# kilo.net
KiCad netlist of a schematic drawn in EAGLE
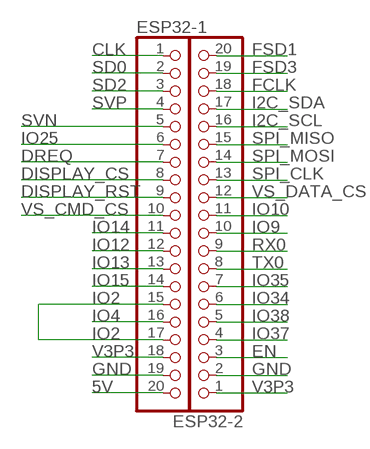
[diagram p0: schematic, sheet 1]
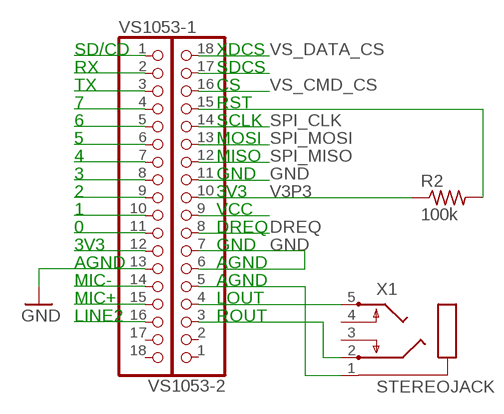
[diagram p1: schematic, sheet 2]
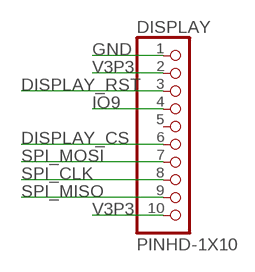
[diagram p2: schematic, sheet 3]
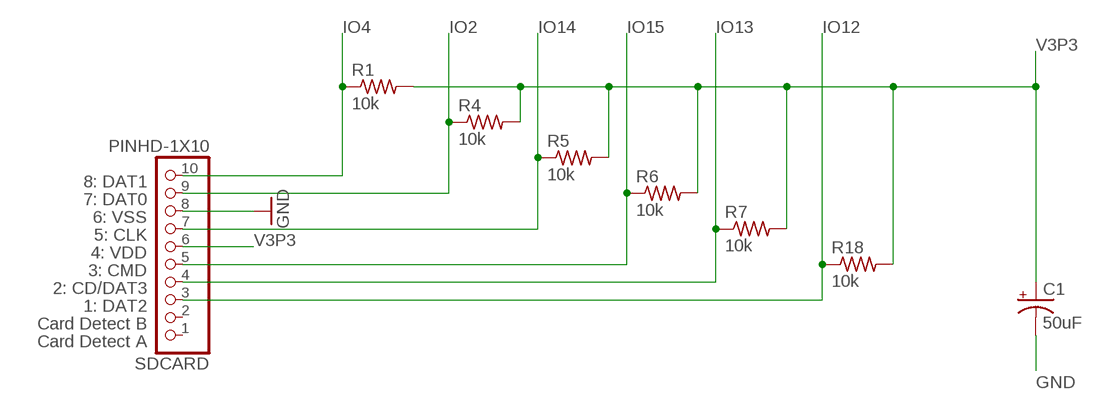
[diagram p3: schematic, sheet 4]
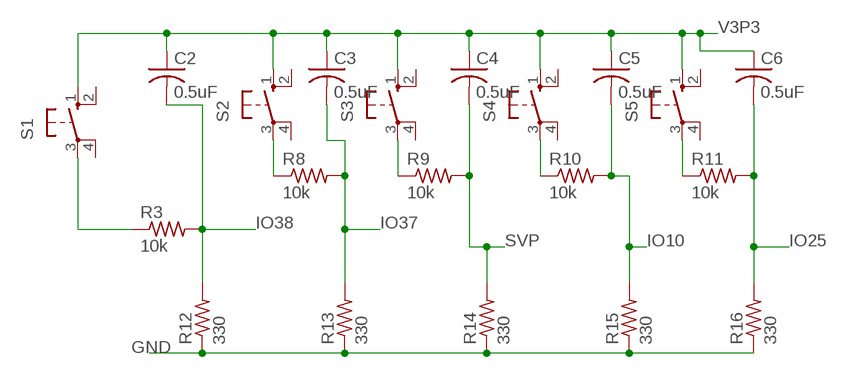
[diagram p4: schematic, sheet 5]

(export (version "E")
  (design (tool "Eeschema 10.0.6"))
  (components
    (comp (ref "C1")
      (value "50uF")
      (footprint "eagle-import:E2,5-7")
      (libsource (lib "eagle-import") (part "CPOL-USE2.5-7"))
    )
    (comp (ref "R1")
      (value "10k")
      (footprint "eagle-import:0207_10")
      (libsource (lib "eagle-import") (part "R-US_0207/10"))
    )
    (comp (ref "R4")
      (value "10k")
      (footprint "eagle-import:0207_10")
      (libsource (lib "eagle-import") (part "R-US_0207/10"))
    )
    (comp (ref "R5")
      (value "10k")
      (footprint "eagle-import:0207_10")
      (libsource (lib "eagle-import") (part "R-US_0207/10"))
    )
    (comp (ref "R6")
      (value "10k")
      (footprint "eagle-import:0207_10")
      (libsource (lib "eagle-import") (part "R-US_0207/10"))
    )
    (comp (ref "R7")
      (value "10k")
      (footprint "eagle-import:0207_10")
      (libsource (lib "eagle-import") (part "R-US_0207/10"))
    )
    (comp (ref "R18")
      (value "10k")
      (footprint "eagle-import:0207_10")
      (libsource (lib "eagle-import") (part "R-US_0207/10"))
    )
    (comp (ref "SDCARD")
      (value "PINHD-1X10")
      (footprint "eagle-import:1X10-BIG")
      (libsource (lib "eagle-import") (part "PINHD-1X10"))
    )
    (comp (ref "R2")
      (value "100k")
      (footprint "eagle-import:0207_10")
      (libsource (lib "eagle-import") (part "R-US_0207/10"))
    )
    (comp (ref "VS1053-1")
      (value "PINHD-1X18")
      (footprint "eagle-import:1X18")
      (libsource (lib "eagle-import") (part "PINHD-1X18"))
    )
    (comp (ref "VS1053-2")
      (value "PINHD-1X18")
      (footprint "eagle-import:1X18")
      (libsource (lib "eagle-import") (part "PINHD-1X18"))
    )
    (comp (ref "X1")
      (value "STEREOJACK")
      (footprint "eagle-import:STX3100")
      (libsource (lib "eagle-import") (part "STEREOJACK"))
    )
    (comp (ref "DISPLAY")
      (value "PINHD-1X10")
      (footprint "eagle-import:1X10-BIG")
      (libsource (lib "eagle-import") (part "PINHD-1X10"))
    )
    (comp (ref "C2")
      (value "0.5uF")
      (footprint "eagle-import:C025-024X044")
      (libsource (lib "eagle-import") (part "C-US025-024X044"))
    )
    (comp (ref "C3")
      (value "0.5uF")
      (footprint "eagle-import:C025-024X044")
      (libsource (lib "eagle-import") (part "C-US025-024X044"))
    )
    (comp (ref "C4")
      (value "0.5uF")
      (footprint "eagle-import:C025-024X044")
      (libsource (lib "eagle-import") (part "C-US025-024X044"))
    )
    (comp (ref "C5")
      (value "0.5uF")
      (footprint "eagle-import:C025-024X044")
      (libsource (lib "eagle-import") (part "C-US025-024X044"))
    )
    (comp (ref "C6")
      (value "0.5uF")
      (footprint "eagle-import:C025-024X044")
      (libsource (lib "eagle-import") (part "C-US025-024X044"))
    )
    (comp (ref "R3")
      (value "10k")
      (footprint "eagle-import:0207_10")
      (libsource (lib "eagle-import") (part "R-US_0207/10"))
    )
    (comp (ref "R8")
      (value "10k")
      (footprint "eagle-import:0207_10")
      (libsource (lib "eagle-import") (part "R-US_0207/10"))
    )
    (comp (ref "R9")
      (value "10k")
      (footprint "eagle-import:0207_10")
      (libsource (lib "eagle-import") (part "R-US_0207/10"))
    )
    (comp (ref "R10")
      (value "10k")
      (footprint "eagle-import:0207_10")
      (libsource (lib "eagle-import") (part "R-US_0207/10"))
    )
    (comp (ref "R11")
      (value "10k")
      (footprint "eagle-import:0207_10")
      (libsource (lib "eagle-import") (part "R-US_0207/10"))
    )
    (comp (ref "R12")
      (value "330")
      (footprint "eagle-import:0207_10")
      (libsource (lib "eagle-import") (part "R-US_0207/10"))
    )
    (comp (ref "R13")
      (value "330")
      (footprint "eagle-import:0207_10")
      (libsource (lib "eagle-import") (part "R-US_0207/10"))
    )
    (comp (ref "R14")
      (value "330")
      (footprint "eagle-import:0207_10")
      (libsource (lib "eagle-import") (part "R-US_0207/10"))
    )
    (comp (ref "R15")
      (value "330")
      (footprint "eagle-import:0207_10")
      (libsource (lib "eagle-import") (part "R-US_0207/10"))
    )
    (comp (ref "R16")
      (value "330")
      (footprint "eagle-import:0207_10")
      (libsource (lib "eagle-import") (part "R-US_0207/10"))
    )
    (comp (ref "S1")
      (value "10-XX")
      (footprint "eagle-import:B3F-10XX")
      (fields (field (name "MPN") "B3F-1000"))
      (libsource (lib "eagle-import") (part "10-XX"))
    )
    (comp (ref "S2")
      (value "10-XX")
      (footprint "eagle-import:B3F-10XX")
      (fields (field (name "MPN") "B3F-1000"))
      (libsource (lib "eagle-import") (part "10-XX"))
    )
    (comp (ref "S3")
      (value "10-XX")
      (footprint "eagle-import:B3F-10XX")
      (fields (field (name "MPN") "B3F-1000"))
      (libsource (lib "eagle-import") (part "10-XX"))
    )
    (comp (ref "S4")
      (value "10-XX")
      (footprint "eagle-import:B3F-10XX")
      (fields (field (name "MPN") "B3F-1000"))
      (libsource (lib "eagle-import") (part "10-XX"))
    )
    (comp (ref "S5")
      (value "10-XX")
      (footprint "eagle-import:B3F-10XX")
      (fields (field (name "MPN") "B3F-1000"))
      (libsource (lib "eagle-import") (part "10-XX"))
    )
    (comp (ref "ESP32-1")
      (value "PINHD-1X20")
      (footprint "eagle-import:1X20")
      (libsource (lib "eagle-import") (part "PINHD-1X20"))
    )
    (comp (ref "ESP32-2")
      (value "PINHD-1X20")
      (footprint "eagle-import:1X20")
      (libsource (lib "eagle-import") (part "PINHD-1X20"))
    )
  )
  (nets
    (net (code "1") (name "5V") (class "Default")
      (node (ref "ESP32-1") (pin "20") (pinfunction "20_20") (pintype "passive"))
    )
    (net (code "2") (name "CLK") (class "Default")
      (node (ref "ESP32-1") (pin "1") (pinfunction "1_1") (pintype "passive"))
    )
    (net (code "3") (name "DISPLAY_CS") (class "Default")
      (node (ref "DISPLAY") (pin "6") (pinfunction "6_6") (pintype "passive"))
      (node (ref "ESP32-1") (pin "8") (pinfunction "8_8") (pintype "passive"))
    )
    (net (code "4") (name "DISPLAY_RST") (class "Default")
      (node (ref "DISPLAY") (pin "3") (pinfunction "3_3") (pintype "passive"))
      (node (ref "ESP32-1") (pin "9") (pinfunction "9_9") (pintype "passive"))
    )
    (net (code "5") (name "DREQ") (class "Default")
      (node (ref "ESP32-1") (pin "7") (pinfunction "7_7") (pintype "passive"))
      (node (ref "VS1053-2") (pin "8") (pinfunction "8_8") (pintype "passive"))
    )
    (net (code "6") (name "EN") (class "Default")
      (node (ref "ESP32-2") (pin "3") (pinfunction "3_3") (pintype "passive"))
    )
    (net (code "7") (name "FCLK") (class "Default")
      (node (ref "ESP32-2") (pin "18") (pinfunction "18_18") (pintype "passive"))
    )
    (net (code "8") (name "FSD1") (class "Default")
      (node (ref "ESP32-2") (pin "20") (pinfunction "20_20") (pintype "passive"))
    )
    (net (code "9") (name "FSD3") (class "Default")
      (node (ref "ESP32-2") (pin "19") (pinfunction "19_19") (pintype "passive"))
    )
    (net (code "10") (name "GND") (class "Default")
      (node (ref "C1") (pin "-") (pinfunction "-_-") (pintype "passive"))
      (node (ref "DISPLAY") (pin "1") (pinfunction "1_1") (pintype "passive"))
      (node (ref "ESP32-1") (pin "19") (pinfunction "19_19") (pintype "passive"))
      (node (ref "ESP32-2") (pin "2") (pinfunction "2_2") (pintype "passive"))
      (node (ref "R12") (pin "1") (pinfunction "1_1") (pintype "passive"))
      (node (ref "R13") (pin "1") (pinfunction "1_1") (pintype "passive"))
      (node (ref "R14") (pin "1") (pinfunction "1_1") (pintype "passive"))
      (node (ref "R15") (pin "1") (pinfunction "1_1") (pintype "passive"))
      (node (ref "R16") (pin "1") (pinfunction "1_1") (pintype "passive"))
      (node (ref "SDCARD") (pin "8") (pinfunction "8_8") (pintype "passive"))
      (node (ref "VS1053-1") (pin "13") (pinfunction "13_13") (pintype "passive"))
      (node (ref "VS1053-2") (pin "11") (pinfunction "11_11") (pintype "passive"))
      (node (ref "VS1053-2") (pin "6") (pinfunction "6_6") (pintype "passive"))
      (node (ref "VS1053-2") (pin "7") (pinfunction "7_7") (pintype "passive"))
    )
    (net (code "11") (name "I2C_SCL") (class "Default")
      (node (ref "ESP32-2") (pin "16") (pinfunction "16_16") (pintype "passive"))
    )
    (net (code "12") (name "I2C_SDA") (class "Default")
      (node (ref "ESP32-2") (pin "17") (pinfunction "17_17") (pintype "passive"))
    )
    (net (code "13") (name "IO2") (class "Default")
      (node (ref "ESP32-1") (pin "15") (pinfunction "15_15") (pintype "passive"))
      (node (ref "ESP32-1") (pin "17") (pinfunction "17_17") (pintype "passive"))
      (node (ref "R4") (pin "1") (pinfunction "1_1") (pintype "passive"))
      (node (ref "SDCARD") (pin "9") (pinfunction "9_9") (pintype "passive"))
    )
    (net (code "14") (name "IO4") (class "Default")
      (node (ref "ESP32-1") (pin "16") (pinfunction "16_16") (pintype "passive"))
      (node (ref "R1") (pin "1") (pinfunction "1_1") (pintype "passive"))
      (node (ref "SDCARD") (pin "10") (pinfunction "10_10") (pintype "passive"))
    )
    (net (code "15") (name "IO9") (class "Default")
      (node (ref "DISPLAY") (pin "4") (pinfunction "4_4") (pintype "passive"))
      (node (ref "ESP32-2") (pin "10") (pinfunction "10_10") (pintype "passive"))
    )
    (net (code "16") (name "IO10") (class "Default")
      (node (ref "C5") (pin "2") (pinfunction "2_2") (pintype "passive"))
      (node (ref "ESP32-2") (pin "11") (pinfunction "11_11") (pintype "passive"))
      (node (ref "R10") (pin "2") (pinfunction "2_2") (pintype "passive"))
      (node (ref "R15") (pin "2") (pinfunction "2_2") (pintype "passive"))
    )
    (net (code "17") (name "IO12") (class "Default")
      (node (ref "ESP32-1") (pin "12") (pinfunction "12_12") (pintype "passive"))
      (node (ref "R18") (pin "1") (pinfunction "1_1") (pintype "passive"))
      (node (ref "SDCARD") (pin "3") (pinfunction "3_3") (pintype "passive"))
    )
    (net (code "18") (name "IO13") (class "Default")
      (node (ref "ESP32-1") (pin "13") (pinfunction "13_13") (pintype "passive"))
      (node (ref "R7") (pin "1") (pinfunction "1_1") (pintype "passive"))
      (node (ref "SDCARD") (pin "4") (pinfunction "4_4") (pintype "passive"))
    )
    (net (code "19") (name "IO14") (class "Default")
      (node (ref "ESP32-1") (pin "11") (pinfunction "11_11") (pintype "passive"))
      (node (ref "R5") (pin "1") (pinfunction "1_1") (pintype "passive"))
      (node (ref "SDCARD") (pin "7") (pinfunction "7_7") (pintype "passive"))
    )
    (net (code "20") (name "IO15") (class "Default")
      (node (ref "ESP32-1") (pin "14") (pinfunction "14_14") (pintype "passive"))
      (node (ref "R6") (pin "1") (pinfunction "1_1") (pintype "passive"))
      (node (ref "SDCARD") (pin "5") (pinfunction "5_5") (pintype "passive"))
    )
    (net (code "21") (name "IO25") (class "Default")
      (node (ref "C6") (pin "2") (pinfunction "2_2") (pintype "passive"))
      (node (ref "ESP32-1") (pin "6") (pinfunction "6_6") (pintype "passive"))
      (node (ref "R11") (pin "2") (pinfunction "2_2") (pintype "passive"))
      (node (ref "R16") (pin "2") (pinfunction "2_2") (pintype "passive"))
    )
    (net (code "22") (name "IO34") (class "Default")
      (node (ref "ESP32-2") (pin "6") (pinfunction "6_6") (pintype "passive"))
    )
    (net (code "23") (name "IO35") (class "Default")
      (node (ref "ESP32-2") (pin "7") (pinfunction "7_7") (pintype "passive"))
    )
    (net (code "24") (name "IO37") (class "Default")
      (node (ref "C3") (pin "2") (pinfunction "2_2") (pintype "passive"))
      (node (ref "ESP32-2") (pin "4") (pinfunction "4_4") (pintype "passive"))
      (node (ref "R13") (pin "2") (pinfunction "2_2") (pintype "passive"))
      (node (ref "R8") (pin "2") (pinfunction "2_2") (pintype "passive"))
    )
    (net (code "25") (name "IO38") (class "Default")
      (node (ref "C2") (pin "2") (pinfunction "2_2") (pintype "passive"))
      (node (ref "ESP32-2") (pin "5") (pinfunction "5_5") (pintype "passive"))
      (node (ref "R12") (pin "2") (pinfunction "2_2") (pintype "passive"))
      (node (ref "R3") (pin "2") (pinfunction "2_2") (pintype "passive"))
    )
    (net (code "26") (name "Net-(R2-Pad2)") (class "Default")
      (node (ref "R2") (pin "2") (pinfunction "2_2") (pintype "passive"))
      (node (ref "VS1053-2") (pin "15") (pinfunction "15_15") (pintype "passive"))
    )
    (net (code "27") (name "Net-(S1-P)") (class "Default")
      (node (ref "R3") (pin "1") (pinfunction "1_1") (pintype "passive"))
      (node (ref "S1") (pin "3") (pinfunction "P_3") (pintype "passive"))
    )
    (net (code "28") (name "Net-(S2-P)") (class "Default")
      (node (ref "R8") (pin "1") (pinfunction "1_1") (pintype "passive"))
      (node (ref "S2") (pin "3") (pinfunction "P_3") (pintype "passive"))
    )
    (net (code "29") (name "Net-(S3-P)") (class "Default")
      (node (ref "R9") (pin "1") (pinfunction "1_1") (pintype "passive"))
      (node (ref "S3") (pin "3") (pinfunction "P_3") (pintype "passive"))
    )
    (net (code "30") (name "Net-(S4-P)") (class "Default")
      (node (ref "R10") (pin "1") (pinfunction "1_1") (pintype "passive"))
      (node (ref "S4") (pin "3") (pinfunction "P_3") (pintype "passive"))
    )
    (net (code "31") (name "Net-(S5-P)") (class "Default")
      (node (ref "R11") (pin "1") (pinfunction "1_1") (pintype "passive"))
      (node (ref "S5") (pin "3") (pinfunction "P_3") (pintype "passive"))
    )
    (net (code "32") (name "Net-(VS1053-2-Pad3)") (class "Default")
      (node (ref "VS1053-2") (pin "3") (pinfunction "3_3") (pintype "passive"))
      (node (ref "X1") (pin "2") (pinfunction "2_2") (pintype "passive"))
    )
    (net (code "33") (name "Net-(VS1053-2-Pad4)") (class "Default")
      (node (ref "VS1053-2") (pin "4") (pinfunction "4_4") (pintype "passive"))
      (node (ref "X1") (pin "5") (pinfunction "5_5") (pintype "passive"))
    )
    (net (code "34") (name "Net-(VS1053-2-Pad5)") (class "Default")
      (node (ref "VS1053-2") (pin "5") (pinfunction "5_5") (pintype "passive"))
      (node (ref "X1") (pin "1") (pinfunction "1_1") (pintype "passive"))
    )
    (net (code "35") (name "RX0") (class "Default")
      (node (ref "ESP32-2") (pin "9") (pinfunction "9_9") (pintype "passive"))
    )
    (net (code "36") (name "SD0") (class "Default")
      (node (ref "ESP32-1") (pin "2") (pinfunction "2_2") (pintype "passive"))
    )
    (net (code "37") (name "SD2") (class "Default")
      (node (ref "ESP32-1") (pin "3") (pinfunction "3_3") (pintype "passive"))
    )
    (net (code "38") (name "SPI_CLK") (class "Default")
      (node (ref "DISPLAY") (pin "8") (pinfunction "8_8") (pintype "passive"))
      (node (ref "ESP32-2") (pin "13") (pinfunction "13_13") (pintype "passive"))
      (node (ref "VS1053-2") (pin "14") (pinfunction "14_14") (pintype "passive"))
    )
    (net (code "39") (name "SPI_MISO") (class "Default")
      (node (ref "DISPLAY") (pin "9") (pinfunction "9_9") (pintype "passive"))
      (node (ref "ESP32-2") (pin "15") (pinfunction "15_15") (pintype "passive"))
      (node (ref "VS1053-2") (pin "12") (pinfunction "12_12") (pintype "passive"))
    )
    (net (code "40") (name "SPI_MOSI") (class "Default")
      (node (ref "DISPLAY") (pin "7") (pinfunction "7_7") (pintype "passive"))
      (node (ref "ESP32-2") (pin "14") (pinfunction "14_14") (pintype "passive"))
      (node (ref "VS1053-2") (pin "13") (pinfunction "13_13") (pintype "passive"))
    )
    (net (code "41") (name "SVN") (class "Default")
      (node (ref "ESP32-1") (pin "5") (pinfunction "5_5") (pintype "passive"))
    )
    (net (code "42") (name "SVP") (class "Default")
      (node (ref "C4") (pin "2") (pinfunction "2_2") (pintype "passive"))
      (node (ref "ESP32-1") (pin "4") (pinfunction "4_4") (pintype "passive"))
      (node (ref "R14") (pin "2") (pinfunction "2_2") (pintype "passive"))
      (node (ref "R9") (pin "2") (pinfunction "2_2") (pintype "passive"))
    )
    (net (code "43") (name "TX0") (class "Default")
      (node (ref "ESP32-2") (pin "8") (pinfunction "8_8") (pintype "passive"))
    )
    (net (code "44") (name "V3P3") (class "Default")
      (node (ref "C1") (pin "+") (pinfunction "+_+") (pintype "passive"))
      (node (ref "C2") (pin "1") (pinfunction "1_1") (pintype "passive"))
      (node (ref "C3") (pin "1") (pinfunction "1_1") (pintype "passive"))
      (node (ref "C4") (pin "1") (pinfunction "1_1") (pintype "passive"))
      (node (ref "C5") (pin "1") (pinfunction "1_1") (pintype "passive"))
      (node (ref "C6") (pin "1") (pinfunction "1_1") (pintype "passive"))
      (node (ref "DISPLAY") (pin "10") (pinfunction "10_10") (pintype "passive"))
      (node (ref "DISPLAY") (pin "2") (pinfunction "2_2") (pintype "passive"))
      (node (ref "ESP32-1") (pin "18") (pinfunction "18_18") (pintype "passive"))
      (node (ref "ESP32-2") (pin "1") (pinfunction "1_1") (pintype "passive"))
      (node (ref "R1") (pin "2") (pinfunction "2_2") (pintype "passive"))
      (node (ref "R18") (pin "2") (pinfunction "2_2") (pintype "passive"))
      (node (ref "R2") (pin "1") (pinfunction "1_1") (pintype "passive"))
      (node (ref "R4") (pin "2") (pinfunction "2_2") (pintype "passive"))
      (node (ref "R5") (pin "2") (pinfunction "2_2") (pintype "passive"))
      (node (ref "R6") (pin "2") (pinfunction "2_2") (pintype "passive"))
      (node (ref "R7") (pin "2") (pinfunction "2_2") (pintype "passive"))
      (node (ref "S1") (pin "1") (pinfunction "S_1") (pintype "passive"))
      (node (ref "S2") (pin "1") (pinfunction "S_1") (pintype "passive"))
      (node (ref "S3") (pin "1") (pinfunction "S_1") (pintype "passive"))
      (node (ref "S4") (pin "1") (pinfunction "S_1") (pintype "passive"))
      (node (ref "S5") (pin "1") (pinfunction "S_1") (pintype "passive"))
      (node (ref "SDCARD") (pin "6") (pinfunction "6_6") (pintype "passive"))
      (node (ref "VS1053-2") (pin "10") (pinfunction "10_10") (pintype "passive"))
    )
    (net (code "45") (name "VS_CMD_CS") (class "Default")
      (node (ref "ESP32-1") (pin "10") (pinfunction "10_10") (pintype "passive"))
      (node (ref "VS1053-2") (pin "16") (pinfunction "16_16") (pintype "passive"))
    )
    (net (code "46") (name "VS_DATA_CS") (class "Default")
      (node (ref "ESP32-2") (pin "12") (pinfunction "12_12") (pintype "passive"))
      (node (ref "VS1053-2") (pin "18") (pinfunction "18_18") (pintype "passive"))
    )
    (net (code "47") (name "unconnected-(DISPLAY-Pad5)") (class "Default")
      (node (ref "DISPLAY") (pin "5") (pinfunction "5_5") (pintype "passive"))
    )
    (net (code "48") (name "unconnected-(S1-P1-Pad4)") (class "Default")
      (node (ref "S1") (pin "4") (pinfunction "P1_4") (pintype "passive"))
    )
    (net (code "49") (name "unconnected-(S1-S1-Pad2)") (class "Default")
      (node (ref "S1") (pin "2") (pinfunction "S1_2") (pintype "passive"))
    )
    (net (code "50") (name "unconnected-(S2-P1-Pad4)") (class "Default")
      (node (ref "S2") (pin "4") (pinfunction "P1_4") (pintype "passive"))
    )
    (net (code "51") (name "unconnected-(S2-S1-Pad2)") (class "Default")
      (node (ref "S2") (pin "2") (pinfunction "S1_2") (pintype "passive"))
    )
    (net (code "52") (name "unconnected-(S3-P1-Pad4)") (class "Default")
      (node (ref "S3") (pin "4") (pinfunction "P1_4") (pintype "passive"))
    )
    (net (code "53") (name "unconnected-(S3-S1-Pad2)") (class "Default")
      (node (ref "S3") (pin "2") (pinfunction "S1_2") (pintype "passive"))
    )
    (net (code "54") (name "unconnected-(S4-P1-Pad4)") (class "Default")
      (node (ref "S4") (pin "4") (pinfunction "P1_4") (pintype "passive"))
    )
    (net (code "55") (name "unconnected-(S4-S1-Pad2)") (class "Default")
      (node (ref "S4") (pin "2") (pinfunction "S1_2") (pintype "passive"))
    )
    (net (code "56") (name "unconnected-(S5-P1-Pad4)") (class "Default")
      (node (ref "S5") (pin "4") (pinfunction "P1_4") (pintype "passive"))
    )
    (net (code "57") (name "unconnected-(S5-S1-Pad2)") (class "Default")
      (node (ref "S5") (pin "2") (pinfunction "S1_2") (pintype "passive"))
    )
    (net (code "58") (name "unconnected-(SDCARD-Pad1)") (class "Default")
      (node (ref "SDCARD") (pin "1") (pinfunction "1_1") (pintype "passive"))
    )
    (net (code "59") (name "unconnected-(SDCARD-Pad2)") (class "Default")
      (node (ref "SDCARD") (pin "2") (pinfunction "2_2") (pintype "passive"))
    )
    (net (code "60") (name "unconnected-(VS1053-1-Pad1)") (class "Default")
      (node (ref "VS1053-1") (pin "1") (pinfunction "1_1") (pintype "passive"))
    )
    (net (code "61") (name "unconnected-(VS1053-1-Pad2)") (class "Default")
      (node (ref "VS1053-1") (pin "2") (pinfunction "2_2") (pintype "passive"))
    )
    (net (code "62") (name "unconnected-(VS1053-1-Pad3)") (class "Default")
      (node (ref "VS1053-1") (pin "3") (pinfunction "3_3") (pintype "passive"))
    )
    (net (code "63") (name "unconnected-(VS1053-1-Pad4)") (class "Default")
      (node (ref "VS1053-1") (pin "4") (pinfunction "4_4") (pintype "passive"))
    )
    (net (code "64") (name "unconnected-(VS1053-1-Pad5)") (class "Default")
      (node (ref "VS1053-1") (pin "5") (pinfunction "5_5") (pintype "passive"))
    )
    (net (code "65") (name "unconnected-(VS1053-1-Pad6)") (class "Default")
      (node (ref "VS1053-1") (pin "6") (pinfunction "6_6") (pintype "passive"))
    )
    (net (code "66") (name "unconnected-(VS1053-1-Pad7)") (class "Default")
      (node (ref "VS1053-1") (pin "7") (pinfunction "7_7") (pintype "passive"))
    )
    (net (code "67") (name "unconnected-(VS1053-1-Pad8)") (class "Default")
      (node (ref "VS1053-1") (pin "8") (pinfunction "8_8") (pintype "passive"))
    )
    (net (code "68") (name "unconnected-(VS1053-1-Pad9)") (class "Default")
      (node (ref "VS1053-1") (pin "9") (pinfunction "9_9") (pintype "passive"))
    )
    (net (code "69") (name "unconnected-(VS1053-1-Pad10)") (class "Default")
      (node (ref "VS1053-1") (pin "10") (pinfunction "10_10") (pintype "passive"))
    )
    (net (code "70") (name "unconnected-(VS1053-1-Pad11)") (class "Default")
      (node (ref "VS1053-1") (pin "11") (pinfunction "11_11") (pintype "passive"))
    )
    (net (code "71") (name "unconnected-(VS1053-1-Pad12)") (class "Default")
      (node (ref "VS1053-1") (pin "12") (pinfunction "12_12") (pintype "passive"))
    )
    (net (code "72") (name "unconnected-(VS1053-1-Pad14)") (class "Default")
      (node (ref "VS1053-1") (pin "14") (pinfunction "14_14") (pintype "passive"))
    )
    (net (code "73") (name "unconnected-(VS1053-1-Pad15)") (class "Default")
      (node (ref "VS1053-1") (pin "15") (pinfunction "15_15") (pintype "passive"))
    )
    (net (code "74") (name "unconnected-(VS1053-1-Pad16)") (class "Default")
      (node (ref "VS1053-1") (pin "16") (pinfunction "16_16") (pintype "passive"))
    )
    (net (code "75") (name "unconnected-(VS1053-1-Pad17)") (class "Default")
      (node (ref "VS1053-1") (pin "17") (pinfunction "17_17") (pintype "passive"))
    )
    (net (code "76") (name "unconnected-(VS1053-1-Pad18)") (class "Default")
      (node (ref "VS1053-1") (pin "18") (pinfunction "18_18") (pintype "passive"))
    )
    (net (code "77") (name "unconnected-(VS1053-2-Pad1)") (class "Default")
      (node (ref "VS1053-2") (pin "1") (pinfunction "1_1") (pintype "passive"))
    )
    (net (code "78") (name "unconnected-(VS1053-2-Pad2)") (class "Default")
      (node (ref "VS1053-2") (pin "2") (pinfunction "2_2") (pintype "passive"))
    )
    (net (code "79") (name "unconnected-(VS1053-2-Pad9)") (class "Default")
      (node (ref "VS1053-2") (pin "9") (pinfunction "9_9") (pintype "passive"))
    )
    (net (code "80") (name "unconnected-(VS1053-2-Pad17)") (class "Default")
      (node (ref "VS1053-2") (pin "17") (pinfunction "17_17") (pintype "passive"))
    )
    (net (code "81") (name "unconnected-(X1-Pad3)") (class "Default")
      (node (ref "X1") (pin "3") (pinfunction "3_3") (pintype "passive"))
    )
    (net (code "82") (name "unconnected-(X1-Pad4)") (class "Default")
      (node (ref "X1") (pin "4") (pinfunction "4_4") (pintype "passive"))
    )
  )
)
